# 03_HMI_Screen.net
KiCad netlist of a schematic drawn in Altium Designer
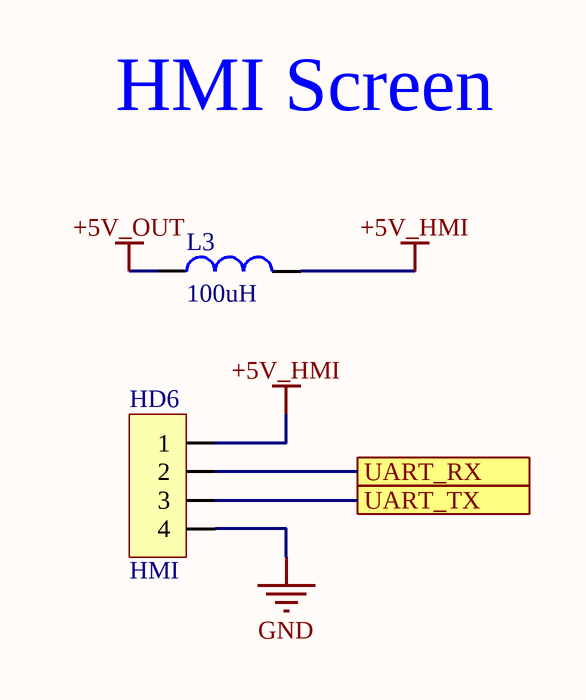
[diagram p0: [03] HMI Screen.SchDoc]

(export (version "E")
  (design (tool "Eeschema 10.0.6"))
  (components
    (comp (ref "HD6")
      (value "HMI")
      (footprint "CON_4P")
      (fields
        (field (name "MANUFACTURER") "Würth Elektronik eiSos GmbH")
        (field (name "PARTNO") "613004143121")
        (field (name "CREATED BY") "Karrer Zheng")
      )
      (libsource (lib "My Library") (part "JP4"))
    )
    (comp (ref "L3")
      (value "100uH")
      (footprint "RES-SMD-0805")
      (description "Inductor")
      (libsource (lib "My Library") (part "Inductor"))
    )
  )
  (nets
    (net (code "1") (name "+5V_HMI") (class "Default")
      (node (ref "HD6") (pin "1") (pinfunction "1_1") (pintype "passive"))
      (node (ref "L3") (pin "2") (pinfunction "2_2") (pintype "passive"))
    )
    (net (code "2") (name "+5V_OUT") (class "Default")
      (node (ref "L3") (pin "1") (pinfunction "1_1") (pintype "passive"))
    )
    (net (code "3") (name "/UART_RX") (class "Default")
      (node (ref "HD6") (pin "2") (pinfunction "2_2") (pintype "passive"))
    )
    (net (code "4") (name "/UART_TX") (class "Default")
      (node (ref "HD6") (pin "3") (pinfunction "3_3") (pintype "passive"))
    )
    (net (code "5") (name "GND") (class "Default")
      (node (ref "HD6") (pin "4") (pinfunction "4_4") (pintype "passive"))
    )
  )
)
